# CSX_Capsense.net
KiCad netlist of a schematic drawn in Altium Designer
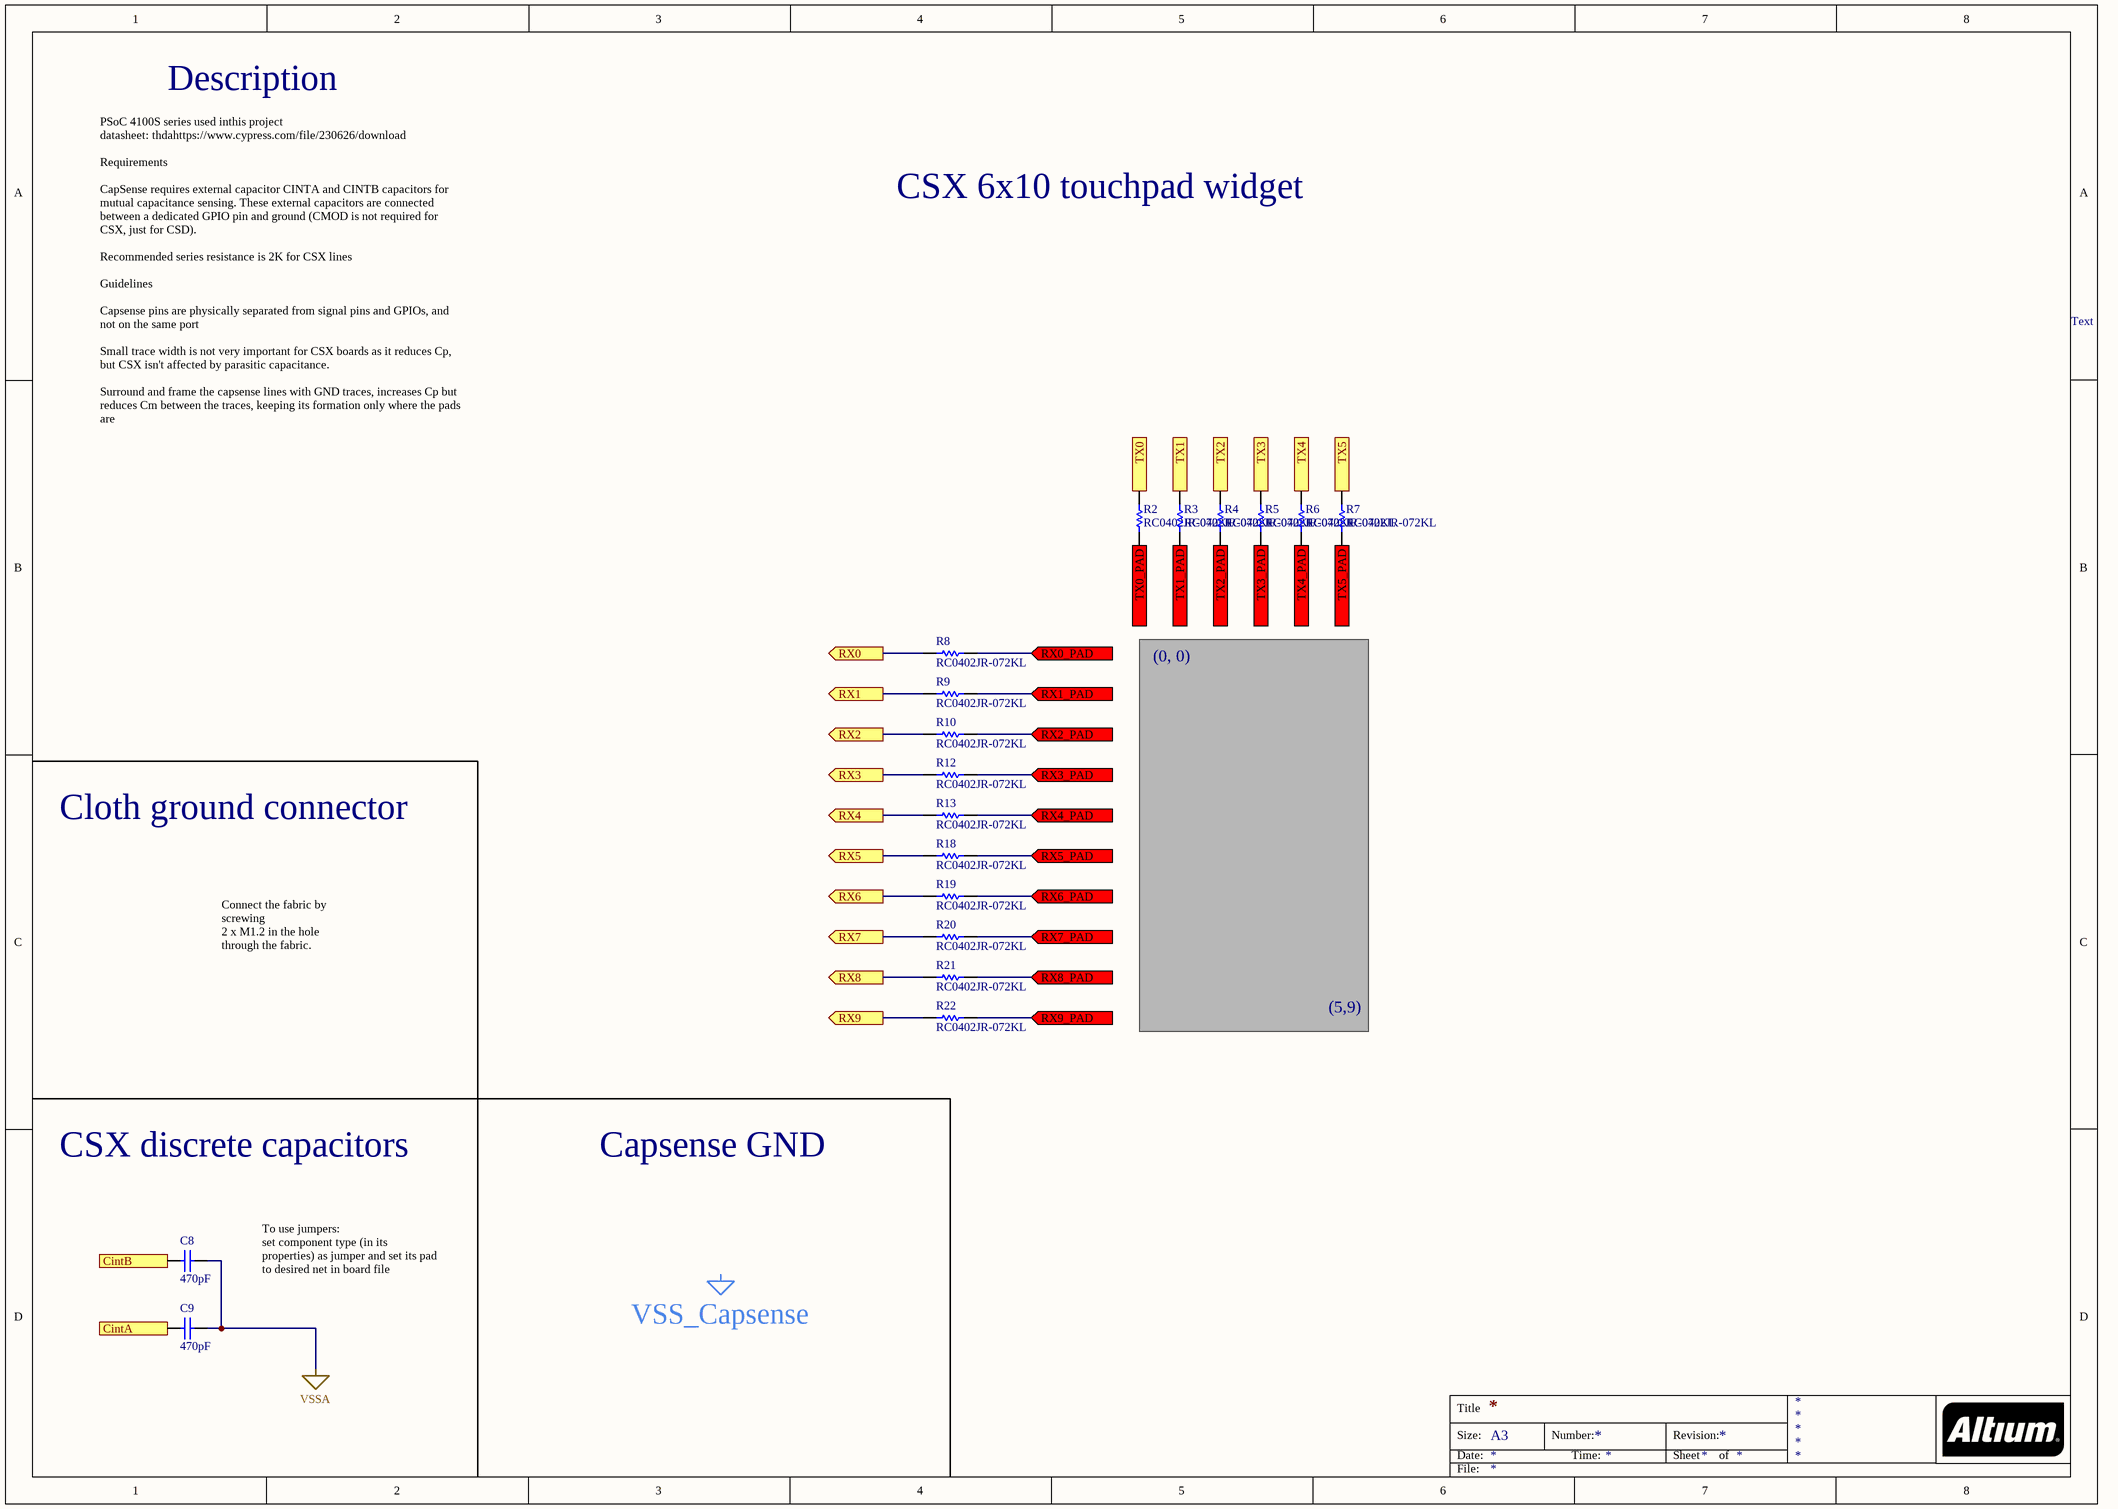
[diagram p0: CSX_Capsense.SchDoc]

(export (version "E")
  (design (tool "Eeschema 10.0.6"))
  (components
    (comp (ref "C8")
      (value "470pF")
      (footprint "CAPC0603(1608)100_N")
      (description "CAP 470pF 10V ±10% 0603 (1608 Metric) Thickness 1mm SMD")
      (fields (field (name "TOLERANCE") "Â±10%"))
      (libsource (lib "Altium Content Vault") (part "CAP"))
    )
    (comp (ref "C9")
      (value "470pF")
      (footprint "CAPC0603(1608)100_N")
      (description "CAP 470pF 10V ±10% 0603 (1608 Metric) Thickness 1mm SMD")
      (fields (field (name "TOLERANCE") "Â±10%"))
      (libsource (lib "Altium Content Vault") (part "CAP"))
    )
    (comp (ref "R2")
      (value "RC0402JR-072KL")
      (footprint "RESC1005X40X25ML05T10")
      (fields (field (name "MANUFACTURER") "Yageo / Phycomp"))
      (libsource (lib "Altium Content Vault") (part "RES"))
    )
    (comp (ref "R3")
      (value "RC0402JR-072KL")
      (footprint "RESC1005X40X25ML05T10")
      (fields (field (name "MANUFACTURER") "Yageo / Phycomp"))
      (libsource (lib "Altium Content Vault") (part "RES"))
    )
    (comp (ref "R4")
      (value "RC0402JR-072KL")
      (footprint "RESC1005X40X25ML05T10")
      (fields (field (name "MANUFACTURER") "Yageo / Phycomp"))
      (libsource (lib "Altium Content Vault") (part "RES"))
    )
    (comp (ref "R5")
      (value "RC0402JR-072KL")
      (footprint "RESC1005X40X25ML05T10")
      (fields (field (name "MANUFACTURER") "Yageo / Phycomp"))
      (libsource (lib "Altium Content Vault") (part "RES"))
    )
    (comp (ref "R6")
      (value "RC0402JR-072KL")
      (footprint "RESC1005X40X25ML05T10")
      (fields (field (name "MANUFACTURER") "Yageo / Phycomp"))
      (libsource (lib "Altium Content Vault") (part "RES"))
    )
    (comp (ref "R7")
      (value "RC0402JR-072KL")
      (footprint "RESC1005X40X25ML05T10")
      (fields (field (name "MANUFACTURER") "Yageo / Phycomp"))
      (libsource (lib "Altium Content Vault") (part "RES"))
    )
    (comp (ref "R8")
      (value "RC0402JR-072KL")
      (footprint "RESC1005X40X25ML05T10")
      (fields (field (name "MANUFACTURER") "Yageo / Phycomp"))
      (libsource (lib "Altium Content Vault") (part "RES"))
    )
    (comp (ref "R9")
      (value "RC0402JR-072KL")
      (footprint "RESC1005X40X25ML05T10")
      (fields (field (name "MANUFACTURER") "Yageo / Phycomp"))
      (libsource (lib "Altium Content Vault") (part "RES"))
    )
    (comp (ref "R10")
      (value "RC0402JR-072KL")
      (footprint "RESC1005X40X25ML05T10")
      (fields (field (name "MANUFACTURER") "Yageo / Phycomp"))
      (libsource (lib "Altium Content Vault") (part "RES"))
    )
    (comp (ref "R12")
      (value "RC0402JR-072KL")
      (footprint "RESC1005X40X25ML05T10")
      (fields (field (name "MANUFACTURER") "Yageo / Phycomp"))
      (libsource (lib "Altium Content Vault") (part "RES"))
    )
    (comp (ref "R13")
      (value "RC0402JR-072KL")
      (footprint "RESC1005X40X25ML05T10")
      (fields (field (name "MANUFACTURER") "Yageo / Phycomp"))
      (libsource (lib "Altium Content Vault") (part "RES"))
    )
    (comp (ref "R18")
      (value "RC0402JR-072KL")
      (footprint "RESC1005X40X25ML05T10")
      (fields (field (name "MANUFACTURER") "Yageo / Phycomp"))
      (libsource (lib "Altium Content Vault") (part "RES"))
    )
    (comp (ref "R19")
      (value "RC0402JR-072KL")
      (footprint "RESC1005X40X25ML05T10")
      (fields (field (name "MANUFACTURER") "Yageo / Phycomp"))
      (libsource (lib "Altium Content Vault") (part "RES"))
    )
    (comp (ref "R20")
      (value "RC0402JR-072KL")
      (footprint "RESC1005X40X25ML05T10")
      (fields (field (name "MANUFACTURER") "Yageo / Phycomp"))
      (libsource (lib "Altium Content Vault") (part "RES"))
    )
    (comp (ref "R21")
      (value "RC0402JR-072KL")
      (footprint "RESC1005X40X25ML05T10")
      (fields (field (name "MANUFACTURER") "Yageo / Phycomp"))
      (libsource (lib "Altium Content Vault") (part "RES"))
    )
    (comp (ref "R22")
      (value "RC0402JR-072KL")
      (footprint "RESC1005X40X25ML05T10")
      (fields (field (name "MANUFACTURER") "Yageo / Phycomp"))
      (libsource (lib "Altium Content Vault") (part "RES"))
    )
  )
  (nets
    (net (code "1") (name "/CintA") (class "Default")
      (node (ref "C9") (pin "1") (pinfunction "1_1") (pintype "passive"))
    )
    (net (code "2") (name "/CintB") (class "Default")
      (node (ref "C8") (pin "1") (pinfunction "1_1") (pintype "passive"))
    )
    (net (code "3") (name "/RX0") (class "Default")
      (node (ref "R8") (pin "1") (pinfunction "1_1") (pintype "passive"))
    )
    (net (code "4") (name "/RX0_PAD") (class "Default")
      (node (ref "R8") (pin "2") (pinfunction "2_2") (pintype "passive"))
    )
    (net (code "5") (name "/RX1") (class "Default")
      (node (ref "R9") (pin "1") (pinfunction "1_1") (pintype "passive"))
    )
    (net (code "6") (name "/RX1_PAD") (class "Default")
      (node (ref "R9") (pin "2") (pinfunction "2_2") (pintype "passive"))
    )
    (net (code "7") (name "/RX2") (class "Default")
      (node (ref "R10") (pin "1") (pinfunction "1_1") (pintype "passive"))
    )
    (net (code "8") (name "/RX2_PAD") (class "Default")
      (node (ref "R10") (pin "2") (pinfunction "2_2") (pintype "passive"))
    )
    (net (code "9") (name "/RX3") (class "Default")
      (node (ref "R12") (pin "1") (pinfunction "1_1") (pintype "passive"))
    )
    (net (code "10") (name "/RX3_PAD") (class "Default")
      (node (ref "R12") (pin "2") (pinfunction "2_2") (pintype "passive"))
    )
    (net (code "11") (name "/RX4") (class "Default")
      (node (ref "R13") (pin "1") (pinfunction "1_1") (pintype "passive"))
    )
    (net (code "12") (name "/RX4_PAD") (class "Default")
      (node (ref "R13") (pin "2") (pinfunction "2_2") (pintype "passive"))
    )
    (net (code "13") (name "/RX5") (class "Default")
      (node (ref "R18") (pin "1") (pinfunction "1_1") (pintype "passive"))
    )
    (net (code "14") (name "/RX5_PAD") (class "Default")
      (node (ref "R18") (pin "2") (pinfunction "2_2") (pintype "passive"))
    )
    (net (code "15") (name "/RX6") (class "Default")
      (node (ref "R19") (pin "1") (pinfunction "1_1") (pintype "passive"))
    )
    (net (code "16") (name "/RX6_PAD") (class "Default")
      (node (ref "R19") (pin "2") (pinfunction "2_2") (pintype "passive"))
    )
    (net (code "17") (name "/RX7") (class "Default")
      (node (ref "R20") (pin "1") (pinfunction "1_1") (pintype "passive"))
    )
    (net (code "18") (name "/RX7_PAD") (class "Default")
      (node (ref "R20") (pin "2") (pinfunction "2_2") (pintype "passive"))
    )
    (net (code "19") (name "/RX8") (class "Default")
      (node (ref "R21") (pin "1") (pinfunction "1_1") (pintype "passive"))
    )
    (net (code "20") (name "/RX8_PAD") (class "Default")
      (node (ref "R21") (pin "2") (pinfunction "2_2") (pintype "passive"))
    )
    (net (code "21") (name "/RX9") (class "Default")
      (node (ref "R22") (pin "1") (pinfunction "1_1") (pintype "passive"))
    )
    (net (code "22") (name "/RX9_PAD") (class "Default")
      (node (ref "R22") (pin "2") (pinfunction "2_2") (pintype "passive"))
    )
    (net (code "23") (name "/TX0") (class "Default")
      (node (ref "R2") (pin "2") (pinfunction "2_2") (pintype "passive"))
    )
    (net (code "24") (name "/TX0_PAD") (class "Default")
      (node (ref "R2") (pin "1") (pinfunction "1_1") (pintype "passive"))
    )
    (net (code "25") (name "/TX1") (class "Default")
      (node (ref "R3") (pin "2") (pinfunction "2_2") (pintype "passive"))
    )
    (net (code "26") (name "/TX1_PAD") (class "Default")
      (node (ref "R3") (pin "1") (pinfunction "1_1") (pintype "passive"))
    )
    (net (code "27") (name "/TX2") (class "Default")
      (node (ref "R4") (pin "2") (pinfunction "2_2") (pintype "passive"))
    )
    (net (code "28") (name "/TX2_PAD") (class "Default")
      (node (ref "R4") (pin "1") (pinfunction "1_1") (pintype "passive"))
    )
    (net (code "29") (name "/TX3") (class "Default")
      (node (ref "R5") (pin "2") (pinfunction "2_2") (pintype "passive"))
    )
    (net (code "30") (name "/TX3_PAD") (class "Default")
      (node (ref "R5") (pin "1") (pinfunction "1_1") (pintype "passive"))
    )
    (net (code "31") (name "/TX4") (class "Default")
      (node (ref "R6") (pin "2") (pinfunction "2_2") (pintype "passive"))
    )
    (net (code "32") (name "/TX4_PAD") (class "Default")
      (node (ref "R6") (pin "1") (pinfunction "1_1") (pintype "passive"))
    )
    (net (code "33") (name "/TX5") (class "Default")
      (node (ref "R7") (pin "2") (pinfunction "2_2") (pintype "passive"))
    )
    (net (code "34") (name "/TX5_PAD") (class "Default")
      (node (ref "R7") (pin "1") (pinfunction "1_1") (pintype "passive"))
    )
    (net (code "35") (name "VSSA") (class "Default")
      (node (ref "C8") (pin "2") (pinfunction "2_2") (pintype "passive"))
      (node (ref "C9") (pin "2") (pinfunction "2_2") (pintype "passive"))
    )
  )
)
